# GS_CCM_R11.net
KiCad netlist of a schematic drawn in EAGLE
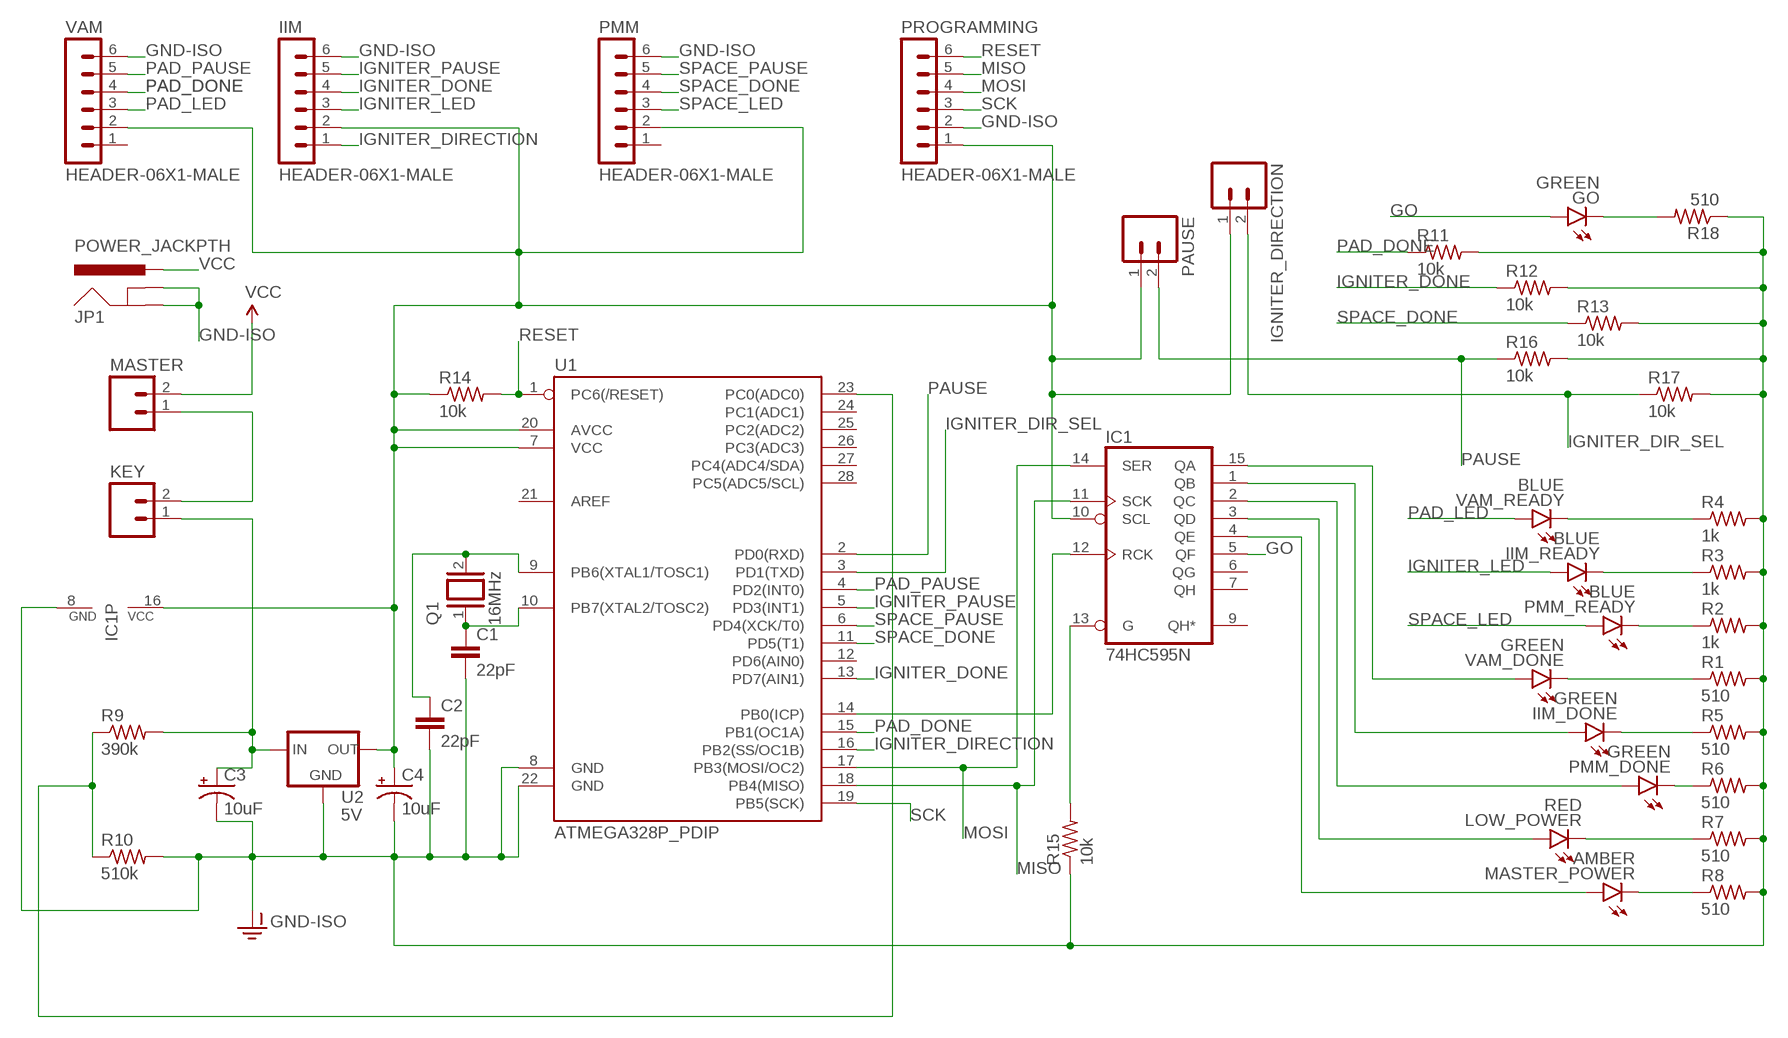
[diagram p0: schematic, sheet 1]

(export (version "E")
  (design (tool "Eeschema 10.0.6"))
  (components
    (comp (ref "C1")
      (value "22pF")
      (footprint "eagle-import:CAP-PTH-5MM")
      (libsource (lib "eagle-import") (part "CAPPTH1"))
    )
    (comp (ref "C2")
      (value "22pF")
      (footprint "eagle-import:CAP-PTH-5MM")
      (libsource (lib "eagle-import") (part "CAPPTH1"))
    )
    (comp (ref "C3")
      (value "10uF")
      (footprint "eagle-import:CPOL-RADIAL-10UF-25V")
      (libsource (lib "eagle-import") (part "CAP_POLPTH2"))
    )
    (comp (ref "C4")
      (value "10uF")
      (footprint "eagle-import:CPOL-RADIAL-10UF-25V")
      (libsource (lib "eagle-import") (part "CAP_POLPTH2"))
    )
    (comp (ref "GO")
      (value "GREEN")
      (footprint "eagle-import:LED5MM")
      (libsource (lib "eagle-import") (part "LED5MM"))
    )
    (comp (ref "IC1")
      (value "74HC595N")
      (footprint "eagle-import:DIL16")
      (libsource (lib "eagle-import") (part "74595NHC"))
    )
    (comp (ref "IGNITER_DIRECTION")
      (value "M02LOCK")
      (footprint "eagle-import:1X02_LOCK")
      (libsource (lib "eagle-import") (part "M02LOCK"))
    )
    (comp (ref "IIM")
      (value "HEADER-06X1-MALE")
      (footprint "eagle-import:06X1-PTH")
      (libsource (lib "eagle-import") (part "HEADER-06X1?-MALE"))
    )
    (comp (ref "IIM_DONE")
      (value "GREEN")
      (footprint "eagle-import:LED5MM")
      (libsource (lib "eagle-import") (part "LED5MM"))
    )
    (comp (ref "IIM_READY")
      (value "BLUE")
      (footprint "eagle-import:LED5MM")
      (libsource (lib "eagle-import") (part "LED5MM"))
    )
    (comp (ref "JP1")
      (value "POWER_JACKPTH")
      (footprint "eagle-import:POWER_JACK_PTH")
      (libsource (lib "eagle-import") (part "POWER_JACKPTH"))
    )
    (comp (ref "KEY")
      (value "M02LOCK")
      (footprint "eagle-import:1X02_LOCK")
      (libsource (lib "eagle-import") (part "M02LOCK"))
    )
    (comp (ref "LOW_POWER")
      (value "RED")
      (footprint "eagle-import:LED5MM")
      (libsource (lib "eagle-import") (part "LED5MM"))
    )
    (comp (ref "MASTER")
      (value "M02LOCK")
      (footprint "eagle-import:1X02_LOCK")
      (libsource (lib "eagle-import") (part "M02LOCK"))
    )
    (comp (ref "MASTER_POWER")
      (value "AMBER")
      (footprint "eagle-import:LED5MM")
      (libsource (lib "eagle-import") (part "LED5MM"))
    )
    (comp (ref "PAUSE")
      (value "M02LOCK")
      (footprint "eagle-import:1X02_LOCK")
      (libsource (lib "eagle-import") (part "M02LOCK"))
    )
    (comp (ref "PMM")
      (value "HEADER-06X1-MALE")
      (footprint "eagle-import:06X1-PTH")
      (libsource (lib "eagle-import") (part "HEADER-06X1?-MALE"))
    )
    (comp (ref "PMM_DONE")
      (value "GREEN")
      (footprint "eagle-import:LED5MM")
      (libsource (lib "eagle-import") (part "LED5MM"))
    )
    (comp (ref "PMM_READY")
      (value "BLUE")
      (footprint "eagle-import:LED5MM")
      (libsource (lib "eagle-import") (part "LED5MM"))
    )
    (comp (ref "PROGRAMMING")
      (value "HEADER-06X1-MALE")
      (footprint "eagle-import:06X1-PTH")
      (libsource (lib "eagle-import") (part "HEADER-06X1?-MALE"))
    )
    (comp (ref "Q1")
      (value "16MHz")
      (footprint "eagle-import:QS")
      (libsource (lib "eagle-import") (part "XTAL/S"))
    )
    (comp (ref "R1")
      (value "510")
      (footprint "eagle-import:R1206")
      (libsource (lib "eagle-import") (part "R-US_R1206"))
    )
    (comp (ref "R2")
      (value "1k")
      (footprint "eagle-import:R1206")
      (libsource (lib "eagle-import") (part "R-US_R1206"))
    )
    (comp (ref "R3")
      (value "1k")
      (footprint "eagle-import:R1206")
      (libsource (lib "eagle-import") (part "R-US_R1206"))
    )
    (comp (ref "R4")
      (value "1k")
      (footprint "eagle-import:R1206")
      (libsource (lib "eagle-import") (part "R-US_R1206"))
    )
    (comp (ref "R5")
      (value "510")
      (footprint "eagle-import:R1206")
      (libsource (lib "eagle-import") (part "R-US_R1206"))
    )
    (comp (ref "R6")
      (value "510")
      (footprint "eagle-import:R1206")
      (libsource (lib "eagle-import") (part "R-US_R1206"))
    )
    (comp (ref "R7")
      (value "510")
      (footprint "eagle-import:R1206")
      (libsource (lib "eagle-import") (part "R-US_R1206"))
    )
    (comp (ref "R8")
      (value "510")
      (footprint "eagle-import:R1206")
      (libsource (lib "eagle-import") (part "R-US_R1206"))
    )
    (comp (ref "R9")
      (value "390k")
      (footprint "eagle-import:R1206")
      (libsource (lib "eagle-import") (part "R-US_R1206"))
    )
    (comp (ref "R10")
      (value "510k")
      (footprint "eagle-import:R1206")
      (libsource (lib "eagle-import") (part "R-US_R1206"))
    )
    (comp (ref "R11")
      (value "10k")
      (footprint "eagle-import:R1206")
      (libsource (lib "eagle-import") (part "R-US_R1206"))
    )
    (comp (ref "R12")
      (value "10k")
      (footprint "eagle-import:R1206")
      (libsource (lib "eagle-import") (part "R-US_R1206"))
    )
    (comp (ref "R13")
      (value "10k")
      (footprint "eagle-import:R1206")
      (libsource (lib "eagle-import") (part "R-US_R1206"))
    )
    (comp (ref "R14")
      (value "10k")
      (footprint "eagle-import:R1206")
      (libsource (lib "eagle-import") (part "R-US_R1206"))
    )
    (comp (ref "R15")
      (value "10k")
      (footprint "eagle-import:R1206")
      (libsource (lib "eagle-import") (part "R-US_R1206"))
    )
    (comp (ref "R16")
      (value "10k")
      (footprint "eagle-import:R1206")
      (libsource (lib "eagle-import") (part "R-US_R1206"))
    )
    (comp (ref "R17")
      (value "10k")
      (footprint "eagle-import:R1206")
      (libsource (lib "eagle-import") (part "R-US_R1206"))
    )
    (comp (ref "R18")
      (value "510")
      (footprint "eagle-import:R1206")
      (libsource (lib "eagle-import") (part "R-US_R1206"))
    )
    (comp (ref "U1")
      (value "ATMEGA328P_PDIP")
      (footprint "eagle-import:DIL28-3")
      (libsource (lib "eagle-import") (part "ATMEGA328P_PDIP"))
    )
    (comp (ref "U2")
      (value "5V")
      (footprint "eagle-import:78XXS")
      (libsource (lib "eagle-import") (part "78XXS"))
    )
    (comp (ref "VAM")
      (value "HEADER-06X1-MALE")
      (footprint "eagle-import:06X1-PTH")
      (libsource (lib "eagle-import") (part "HEADER-06X1?-MALE"))
    )
    (comp (ref "VAM_DONE")
      (value "GREEN")
      (footprint "eagle-import:LED5MM")
      (libsource (lib "eagle-import") (part "LED5MM"))
    )
    (comp (ref "VAM_READY")
      (value "BLUE")
      (footprint "eagle-import:LED5MM")
      (libsource (lib "eagle-import") (part "LED5MM"))
    )
  )
  (nets
    (net (code "1") (name "/GO") (class "Default")
      (node (ref "GO") (pin "A") (pinfunction "A_A") (pintype "passive"))
      (node (ref "IC1") (pin "5") (pinfunction "QF_5") (pintype "tri_state"))
    )
    (net (code "2") (name "/IGNITER_DIRECTION") (class "Default")
      (node (ref "IIM") (pin "1") (pinfunction "1_1") (pintype "passive"))
      (node (ref "U1") (pin "16") (pinfunction "PB2(SS/OC1B)_16") (pintype "bidirectional"))
    )
    (net (code "3") (name "/IGNITER_DIR_SEL") (class "Default")
      (node (ref "IGNITER_DIRECTION") (pin "2") (pinfunction "2_2") (pintype "passive"))
      (node (ref "R17") (pin "1") (pinfunction "1_1") (pintype "passive"))
      (node (ref "U1") (pin "3") (pinfunction "PD1(TXD)_3") (pintype "bidirectional"))
    )
    (net (code "4") (name "/IGNITER_DONE") (class "Default")
      (node (ref "IIM") (pin "4") (pinfunction "4_4") (pintype "passive"))
      (node (ref "R12") (pin "1") (pinfunction "1_1") (pintype "passive"))
      (node (ref "U1") (pin "13") (pinfunction "PD7(AIN1)_13") (pintype "bidirectional"))
    )
    (net (code "5") (name "/IGNITER_LED") (class "Default")
      (node (ref "IIM") (pin "3") (pinfunction "3_3") (pintype "passive"))
      (node (ref "IIM_READY") (pin "A") (pinfunction "A_A") (pintype "passive"))
    )
    (net (code "6") (name "/IGNITER_PAUSE") (class "Default")
      (node (ref "IIM") (pin "5") (pinfunction "5_5") (pintype "passive"))
      (node (ref "U1") (pin "5") (pinfunction "PD3(INT1)_5") (pintype "bidirectional"))
    )
    (net (code "7") (name "/MISO") (class "Default")
      (node (ref "IC1") (pin "11") (pinfunction "SCK_11") (pintype "input"))
      (node (ref "PROGRAMMING") (pin "5") (pinfunction "5_5") (pintype "passive"))
      (node (ref "U1") (pin "18") (pinfunction "PB4(MISO)_18") (pintype "bidirectional"))
    )
    (net (code "8") (name "/MOSI") (class "Default")
      (node (ref "IC1") (pin "14") (pinfunction "SER_14") (pintype "input"))
      (node (ref "PROGRAMMING") (pin "4") (pinfunction "4_4") (pintype "passive"))
      (node (ref "U1") (pin "17") (pinfunction "PB3(MOSI/OC2)_17") (pintype "bidirectional"))
    )
    (net (code "9") (name "/PAD_DONE") (class "Default")
      (node (ref "R11") (pin "1") (pinfunction "1_1") (pintype "passive"))
      (node (ref "U1") (pin "15") (pinfunction "PB1(OC1A)_15") (pintype "bidirectional"))
      (node (ref "VAM") (pin "4") (pinfunction "4_4") (pintype "passive"))
    )
    (net (code "10") (name "/PAD_LED") (class "Default")
      (node (ref "VAM") (pin "3") (pinfunction "3_3") (pintype "passive"))
      (node (ref "VAM_READY") (pin "A") (pinfunction "A_A") (pintype "passive"))
    )
    (net (code "11") (name "/PAD_PAUSE") (class "Default")
      (node (ref "U1") (pin "4") (pinfunction "PD2(INT0)_4") (pintype "bidirectional"))
      (node (ref "VAM") (pin "5") (pinfunction "5_5") (pintype "passive"))
    )
    (net (code "12") (name "/PAUSE") (class "Default")
      (node (ref "PAUSE") (pin "2") (pinfunction "2_2") (pintype "passive"))
      (node (ref "R16") (pin "1") (pinfunction "1_1") (pintype "passive"))
      (node (ref "U1") (pin "2") (pinfunction "PD0(RXD)_2") (pintype "bidirectional"))
    )
    (net (code "13") (name "/RESET") (class "Default")
      (node (ref "PROGRAMMING") (pin "6") (pinfunction "6_6") (pintype "passive"))
      (node (ref "R14") (pin "2") (pinfunction "2_2") (pintype "passive"))
      (node (ref "U1") (pin "1") (pinfunction "PC6(/RESET)_1") (pintype "bidirectional"))
    )
    (net (code "14") (name "/SCK") (class "Default")
      (node (ref "PROGRAMMING") (pin "3") (pinfunction "3_3") (pintype "passive"))
      (node (ref "U1") (pin "19") (pinfunction "PB5(SCK)_19") (pintype "bidirectional"))
    )
    (net (code "15") (name "/SPACE_DONE") (class "Default")
      (node (ref "PMM") (pin "4") (pinfunction "4_4") (pintype "passive"))
      (node (ref "R13") (pin "1") (pinfunction "1_1") (pintype "passive"))
      (node (ref "U1") (pin "11") (pinfunction "PD5(T1)_11") (pintype "bidirectional"))
    )
    (net (code "16") (name "/SPACE_LED") (class "Default")
      (node (ref "PMM") (pin "3") (pinfunction "3_3") (pintype "passive"))
      (node (ref "PMM_READY") (pin "A") (pinfunction "A_A") (pintype "passive"))
    )
    (net (code "17") (name "/SPACE_PAUSE") (class "Default")
      (node (ref "PMM") (pin "5") (pinfunction "5_5") (pintype "passive"))
      (node (ref "U1") (pin "6") (pinfunction "PD4(XCK/T0)_6") (pintype "bidirectional"))
    )
    (net (code "18") (name "GND-ISO") (class "Default")
      (node (ref "C1") (pin "2") (pinfunction "2_2") (pintype "passive"))
      (node (ref "C2") (pin "2") (pinfunction "2_2") (pintype "passive"))
      (node (ref "C3") (pin "2") (pinfunction "-_2") (pintype "passive"))
      (node (ref "C4") (pin "2") (pinfunction "-_2") (pintype "passive"))
      (node (ref "IC1") (pin "8") (pinfunction "GND_8") (pintype "power_in"))
      (node (ref "IIM") (pin "6") (pinfunction "6_6") (pintype "passive"))
      (node (ref "JP1") (pin "GND") (pinfunction "GND_GND") (pintype "bidirectional"))
      (node (ref "JP1") (pin "GNDBREAK") (pinfunction "GNDBREAK_GNDBREAK") (pintype "bidirectional"))
      (node (ref "PMM") (pin "6") (pinfunction "6_6") (pintype "passive"))
      (node (ref "PROGRAMMING") (pin "2") (pinfunction "2_2") (pintype "passive"))
      (node (ref "R1") (pin "2") (pinfunction "2_2") (pintype "passive"))
      (node (ref "R10") (pin "2") (pinfunction "2_2") (pintype "passive"))
      (node (ref "R11") (pin "2") (pinfunction "2_2") (pintype "passive"))
      (node (ref "R12") (pin "2") (pinfunction "2_2") (pintype "passive"))
      (node (ref "R13") (pin "2") (pinfunction "2_2") (pintype "passive"))
      (node (ref "R15") (pin "1") (pinfunction "1_1") (pintype "passive"))
      (node (ref "R16") (pin "2") (pinfunction "2_2") (pintype "passive"))
      (node (ref "R17") (pin "2") (pinfunction "2_2") (pintype "passive"))
      (node (ref "R18") (pin "1") (pinfunction "1_1") (pintype "passive"))
      (node (ref "R2") (pin "2") (pinfunction "2_2") (pintype "passive"))
      (node (ref "R3") (pin "2") (pinfunction "2_2") (pintype "passive"))
      (node (ref "R4") (pin "2") (pinfunction "2_2") (pintype "passive"))
      (node (ref "R5") (pin "2") (pinfunction "2_2") (pintype "passive"))
      (node (ref "R6") (pin "2") (pinfunction "2_2") (pintype "passive"))
      (node (ref "R7") (pin "2") (pinfunction "2_2") (pintype "passive"))
      (node (ref "R8") (pin "2") (pinfunction "2_2") (pintype "passive"))
      (node (ref "U1") (pin "22") (pinfunction "GND_22") (pintype "bidirectional"))
      (node (ref "U1") (pin "8") (pinfunction "GND_8") (pintype "bidirectional"))
      (node (ref "U2") (pin "GND") (pinfunction "GND_GND") (pintype "input"))
      (node (ref "VAM") (pin "6") (pinfunction "6_6") (pintype "passive"))
    )
    (net (code "19") (name "Net-(C3-+)") (class "Default")
      (node (ref "C3") (pin "1") (pinfunction "+_1") (pintype "passive"))
      (node (ref "KEY") (pin "1") (pinfunction "1_1") (pintype "passive"))
      (node (ref "R9") (pin "2") (pinfunction "2_2") (pintype "passive"))
      (node (ref "U2") (pin "IN") (pinfunction "IN_IN") (pintype "input"))
    )
    (net (code "20") (name "Net-(C4-+)") (class "Default")
      (node (ref "C4") (pin "1") (pinfunction "+_1") (pintype "passive"))
      (node (ref "IC1") (pin "10") (pinfunction "SCL_10") (pintype "input"))
      (node (ref "IC1") (pin "16") (pinfunction "VCC_16") (pintype "power_in"))
      (node (ref "IGNITER_DIRECTION") (pin "1") (pinfunction "1_1") (pintype "passive"))
      (node (ref "IIM") (pin "2") (pinfunction "2_2") (pintype "passive"))
      (node (ref "PAUSE") (pin "1") (pinfunction "1_1") (pintype "passive"))
      (node (ref "PMM") (pin "2") (pinfunction "2_2") (pintype "passive"))
      (node (ref "PROGRAMMING") (pin "1") (pinfunction "1_1") (pintype "passive"))
      (node (ref "R14") (pin "1") (pinfunction "1_1") (pintype "passive"))
      (node (ref "U1") (pin "20") (pinfunction "AVCC_20") (pintype "bidirectional"))
      (node (ref "U1") (pin "7") (pinfunction "VCC_7") (pintype "bidirectional"))
      (node (ref "U2") (pin "OUT") (pinfunction "OUT_OUT") (pintype "passive"))
      (node (ref "VAM") (pin "2") (pinfunction "2_2") (pintype "passive"))
    )
    (net (code "21") (name "Net-(GO-C)") (class "Default")
      (node (ref "GO") (pin "K") (pinfunction "C_K") (pintype "passive"))
      (node (ref "R18") (pin "2") (pinfunction "2_2") (pintype "passive"))
    )
    (net (code "22") (name "Net-(IC1A-G)") (class "Default")
      (node (ref "IC1") (pin "13") (pinfunction "G_13") (pintype "input"))
      (node (ref "R15") (pin "2") (pinfunction "2_2") (pintype "passive"))
    )
    (net (code "23") (name "Net-(IC1A-QA)") (class "Default")
      (node (ref "IC1") (pin "15") (pinfunction "QA_15") (pintype "tri_state"))
      (node (ref "VAM_DONE") (pin "A") (pinfunction "A_A") (pintype "passive"))
    )
    (net (code "24") (name "Net-(IC1A-QB)") (class "Default")
      (node (ref "IC1") (pin "1") (pinfunction "QB_1") (pintype "tri_state"))
      (node (ref "IIM_DONE") (pin "A") (pinfunction "A_A") (pintype "passive"))
    )
    (net (code "25") (name "Net-(IC1A-QC)") (class "Default")
      (node (ref "IC1") (pin "2") (pinfunction "QC_2") (pintype "tri_state"))
      (node (ref "PMM_DONE") (pin "A") (pinfunction "A_A") (pintype "passive"))
    )
    (net (code "26") (name "Net-(IC1A-QD)") (class "Default")
      (node (ref "IC1") (pin "3") (pinfunction "QD_3") (pintype "tri_state"))
      (node (ref "LOW_POWER") (pin "A") (pinfunction "A_A") (pintype "passive"))
    )
    (net (code "27") (name "Net-(IC1A-QE)") (class "Default")
      (node (ref "IC1") (pin "4") (pinfunction "QE_4") (pintype "tri_state"))
      (node (ref "MASTER_POWER") (pin "A") (pinfunction "A_A") (pintype "passive"))
    )
    (net (code "28") (name "Net-(IC1A-RCK)") (class "Default")
      (node (ref "IC1") (pin "12") (pinfunction "RCK_12") (pintype "input"))
      (node (ref "U1") (pin "14") (pinfunction "PB0(ICP)_14") (pintype "bidirectional"))
    )
    (net (code "29") (name "Net-(IIM_DONE-C)") (class "Default")
      (node (ref "IIM_DONE") (pin "K") (pinfunction "C_K") (pintype "passive"))
      (node (ref "R5") (pin "1") (pinfunction "1_1") (pintype "passive"))
    )
    (net (code "30") (name "Net-(IIM_READY-C)") (class "Default")
      (node (ref "IIM_READY") (pin "K") (pinfunction "C_K") (pintype "passive"))
      (node (ref "R3") (pin "1") (pinfunction "1_1") (pintype "passive"))
    )
    (net (code "31") (name "Net-(KEY-Pad2)") (class "Default")
      (node (ref "KEY") (pin "2") (pinfunction "2_2") (pintype "passive"))
      (node (ref "MASTER") (pin "1") (pinfunction "1_1") (pintype "passive"))
    )
    (net (code "32") (name "Net-(LOW_POWER-C)") (class "Default")
      (node (ref "LOW_POWER") (pin "K") (pinfunction "C_K") (pintype "passive"))
      (node (ref "R7") (pin "1") (pinfunction "1_1") (pintype "passive"))
    )
    (net (code "33") (name "Net-(MASTER_POWER-C)") (class "Default")
      (node (ref "MASTER_POWER") (pin "K") (pinfunction "C_K") (pintype "passive"))
      (node (ref "R8") (pin "1") (pinfunction "1_1") (pintype "passive"))
    )
    (net (code "34") (name "Net-(PMM_DONE-C)") (class "Default")
      (node (ref "PMM_DONE") (pin "K") (pinfunction "C_K") (pintype "passive"))
      (node (ref "R6") (pin "1") (pinfunction "1_1") (pintype "passive"))
    )
    (net (code "35") (name "Net-(PMM_READY-C)") (class "Default")
      (node (ref "PMM_READY") (pin "K") (pinfunction "C_K") (pintype "passive"))
      (node (ref "R2") (pin "1") (pinfunction "1_1") (pintype "passive"))
    )
    (net (code "36") (name "Net-(U1-PB6(XTAL1{slash}TOSC1))") (class "Default")
      (node (ref "C2") (pin "1") (pinfunction "1_1") (pintype "passive"))
      (node (ref "Q1") (pin "2") (pinfunction "2_2") (pintype "passive"))
      (node (ref "U1") (pin "9") (pinfunction "PB6(XTAL1/TOSC1)_9") (pintype "bidirectional"))
    )
    (net (code "37") (name "Net-(U1-PB7(XTAL2{slash}TOSC2))") (class "Default")
      (node (ref "C1") (pin "1") (pinfunction "1_1") (pintype "passive"))
      (node (ref "Q1") (pin "1") (pinfunction "1_1") (pintype "passive"))
      (node (ref "U1") (pin "10") (pinfunction "PB7(XTAL2/TOSC2)_10") (pintype "bidirectional"))
    )
    (net (code "38") (name "Net-(U1-PC0(ADC0))") (class "Default")
      (node (ref "R10") (pin "1") (pinfunction "1_1") (pintype "passive"))
      (node (ref "R9") (pin "1") (pinfunction "1_1") (pintype "passive"))
      (node (ref "U1") (pin "23") (pinfunction "PC0(ADC0)_23") (pintype "bidirectional"))
    )
    (net (code "39") (name "Net-(VAM_DONE-C)") (class "Default")
      (node (ref "R1") (pin "1") (pinfunction "1_1") (pintype "passive"))
      (node (ref "VAM_DONE") (pin "K") (pinfunction "C_K") (pintype "passive"))
    )
    (net (code "40") (name "Net-(VAM_READY-C)") (class "Default")
      (node (ref "R4") (pin "1") (pinfunction "1_1") (pintype "passive"))
      (node (ref "VAM_READY") (pin "K") (pinfunction "C_K") (pintype "passive"))
    )
    (net (code "41") (name "VCC") (class "Default")
      (node (ref "JP1") (pin "PWR") (pinfunction "PWR_PWR") (pintype "bidirectional"))
      (node (ref "MASTER") (pin "2") (pinfunction "2_2") (pintype "passive"))
    )
    (net (code "42") (name "unconnected-(IC1A-QG-Pad6)") (class "Default")
      (node (ref "IC1") (pin "6") (pinfunction "QG_6") (pintype "tri_state"))
    )
    (net (code "43") (name "unconnected-(IC1A-QH*-Pad9)") (class "Default")
      (node (ref "IC1") (pin "9") (pinfunction "QH*_9") (pintype "tri_state"))
    )
    (net (code "44") (name "unconnected-(IC1A-QH-Pad7)") (class "Default")
      (node (ref "IC1") (pin "7") (pinfunction "QH_7") (pintype "tri_state"))
    )
    (net (code "45") (name "unconnected-(PMM-Pad1)") (class "Default")
      (node (ref "PMM") (pin "1") (pinfunction "1_1") (pintype "passive"))
    )
    (net (code "46") (name "unconnected-(U1-AREF-Pad21)") (class "Default")
      (node (ref "U1") (pin "21") (pinfunction "AREF_21") (pintype "bidirectional"))
    )
    (net (code "47") (name "unconnected-(U1-PC1(ADC1)-Pad24)") (class "Default")
      (node (ref "U1") (pin "24") (pinfunction "PC1(ADC1)_24") (pintype "bidirectional"))
    )
    (net (code "48") (name "unconnected-(U1-PC2(ADC2)-Pad25)") (class "Default")
      (node (ref "U1") (pin "25") (pinfunction "PC2(ADC2)_25") (pintype "bidirectional"))
    )
    (net (code "49") (name "unconnected-(U1-PC3(ADC3)-Pad26)") (class "Default")
      (node (ref "U1") (pin "26") (pinfunction "PC3(ADC3)_26") (pintype "bidirectional"))
    )
    (net (code "50") (name "unconnected-(U1-PC4(ADC4{slash}SDA)-Pad27)") (class "Default")
      (node (ref "U1") (pin "27") (pinfunction "PC4(ADC4/SDA)_27") (pintype "bidirectional"))
    )
    (net (code "51") (name "unconnected-(U1-PC5(ADC5{slash}SCL)-Pad28)") (class "Default")
      (node (ref "U1") (pin "28") (pinfunction "PC5(ADC5/SCL)_28") (pintype "bidirectional"))
    )
    (net (code "52") (name "unconnected-(U1-PD6(AIN0)-Pad12)") (class "Default")
      (node (ref "U1") (pin "12") (pinfunction "PD6(AIN0)_12") (pintype "bidirectional"))
    )
    (net (code "53") (name "unconnected-(VAM-Pad1)") (class "Default")
      (node (ref "VAM") (pin "1") (pinfunction "1_1") (pintype "passive"))
    )
  )
)
